# Safety_2019_V_3_0_RTDS.net
KiCad netlist of a schematic drawn in Altium Designer
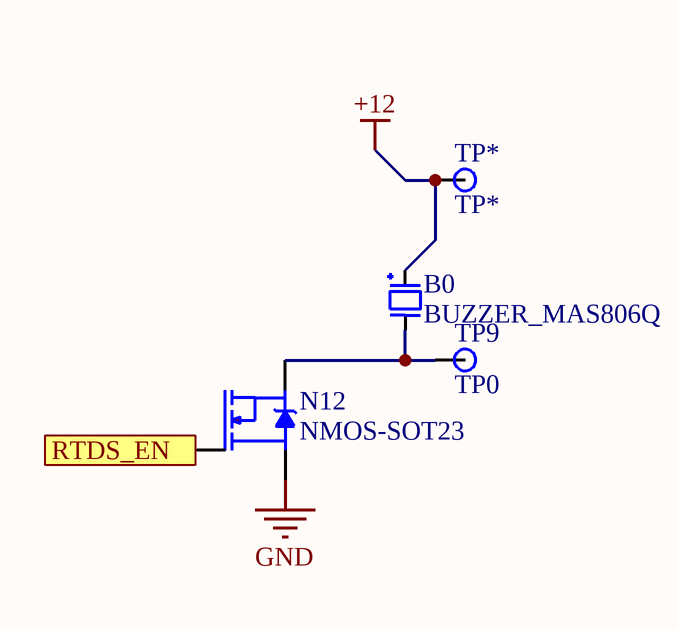
[diagram p0: Safety_2019_V_3_0_RTDS.SchDoc]

(export (version "E")
  (design (tool "Eeschema 10.0.6"))
  (components
    (comp (ref "B0")
      (value "BUZZER_MAS806Q")
      (footprint "BUZZER_MAS806Q")
      (libsource (lib "ife19_Elec_Library") (part "BUZZER_MAS806Q"))
    )
    (comp (ref "N12")
      (value "NMOS-SOT23")
      (footprint "SOT23")
      (libsource (lib "ife19_Elec_Library") (part "NMOS-SOT23"))
    )
    (comp (ref "TP*")
      (value "TP*")
      (footprint "Testpoint")
      (libsource (lib "ife19_Elec_Library") (part "Testpoint"))
    )
    (comp (ref "TP9")
      (value "TP0")
      (footprint "Testpoint")
      (libsource (lib "ife19_Elec_Library") (part "Testpoint"))
    )
  )
  (nets
    (net (code "1") (name "+12") (class "Default")
      (node (ref "B0") (pin "+") (pinfunction "+_+") (pintype "passive"))
      (node (ref "TP*") (pin "1") (pinfunction "1_1") (pintype "passive"))
    )
    (net (code "2") (name "/RTDS_EN") (class "Default")
      (node (ref "N12") (pin "1") (pinfunction "G_1") (pintype "passive"))
    )
    (net (code "3") (name "GND") (class "Default")
      (node (ref "N12") (pin "2") (pinfunction "S_2") (pintype "passive"))
    )
    (net (code "4") (name "Net-(N12-D)") (class "Default")
      (node (ref "B0") (pin "-") (pinfunction "-_-") (pintype "passive"))
      (node (ref "N12") (pin "3") (pinfunction "D_3") (pintype "passive"))
      (node (ref "TP9") (pin "1") (pinfunction "1_1") (pintype "passive"))
    )
  )
)
